# vdriver.net
KiCad netlist of a schematic drawn in Altium Designer
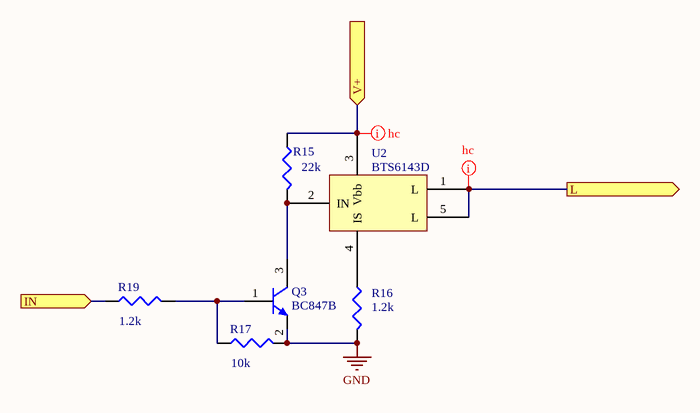
[diagram p0: vdriver.SchDoc]

(export (version "E")
  (design (tool "Eeschema 10.0.6"))
  (components
    (comp (ref "Q3")
      (value "BC847B")
      (footprint "SOT-23_N")
      (description "NPN Bipolar Transistor")
      (fields (field (name "PUBLISHER") "Altium Limited"))
      (libsource (lib "Miscellaneous Devices") (part "NPN"))
    )
    (comp (ref "R15")
      (value "22k")
      (footprint "J1-0603")
      (description "Resistor")
      (fields (field (name "PUBLISHER") "Altium Limited"))
      (libsource (lib "Miscellaneous Devices") (part "Res3"))
    )
    (comp (ref "R16")
      (value "1.2k")
      (footprint "J1-0603")
      (description "Resistor")
      (fields (field (name "PUBLISHER") "Altium Limited"))
      (libsource (lib "Miscellaneous Devices") (part "Res3"))
    )
    (comp (ref "R17")
      (value "10k")
      (footprint "J1-0603")
      (description "Resistor")
      (fields (field (name "PUBLISHER") "Altium Limited"))
      (libsource (lib "Miscellaneous Devices") (part "Res3"))
    )
    (comp (ref "R19")
      (value "1.2k")
      (footprint "J1-0603")
      (description "Resistor")
      (fields (field (name "PUBLISHER") "Altium Limited"))
      (libsource (lib "Miscellaneous Devices") (part "Res3"))
    )
    (comp (ref "U2") (value "BTS6143D") (footprint "BTS6143D") (libsource (lib "misc") (part "BTS6143D")))
  )
  (nets
    (net (code "1") (name "/IN") (class "Default")
      (node (ref "R19") (pin "1") (pinfunction "1_1") (pintype "passive"))
    )
    (net (code "2") (name "/L") (class "Default")
      (node (ref "U2") (pin "1") (pinfunction "L_1") (pintype "passive"))
      (node (ref "U2") (pin "5") (pinfunction "L_5") (pintype "passive"))
    )
    (net (code "3") (name "/V+") (class "Default")
      (node (ref "R15") (pin "1") (pinfunction "1_1") (pintype "passive"))
      (node (ref "U2") (pin "3") (pinfunction "Vbb_3") (pintype "passive"))
    )
    (net (code "4") (name "GND") (class "Default")
      (node (ref "Q3") (pin "2") (pinfunction "E_2") (pintype "passive"))
      (node (ref "R16") (pin "2") (pinfunction "2_2") (pintype "passive"))
      (node (ref "R17") (pin "2") (pinfunction "2_2") (pintype "passive"))
    )
    (net (code "5") (name "Net-(Q3-B)") (class "Default")
      (node (ref "Q3") (pin "1") (pinfunction "B_1") (pintype "passive"))
      (node (ref "R17") (pin "1") (pinfunction "1_1") (pintype "passive"))
      (node (ref "R19") (pin "2") (pinfunction "2_2") (pintype "passive"))
    )
    (net (code "6") (name "Net-(Q3-C)") (class "Default")
      (node (ref "Q3") (pin "3") (pinfunction "C_3") (pintype "passive"))
      (node (ref "R15") (pin "2") (pinfunction "2_2") (pintype "passive"))
      (node (ref "U2") (pin "2") (pinfunction "IN_2") (pintype "passive"))
    )
    (net (code "7") (name "Net-(U2-IS)") (class "Default")
      (node (ref "R16") (pin "1") (pinfunction "1_1") (pintype "passive"))
      (node (ref "U2") (pin "4") (pinfunction "IS_4") (pintype "passive"))
    )
  )
)
